# ATmega32.net
KiCad netlist of a schematic drawn in Altium Designer
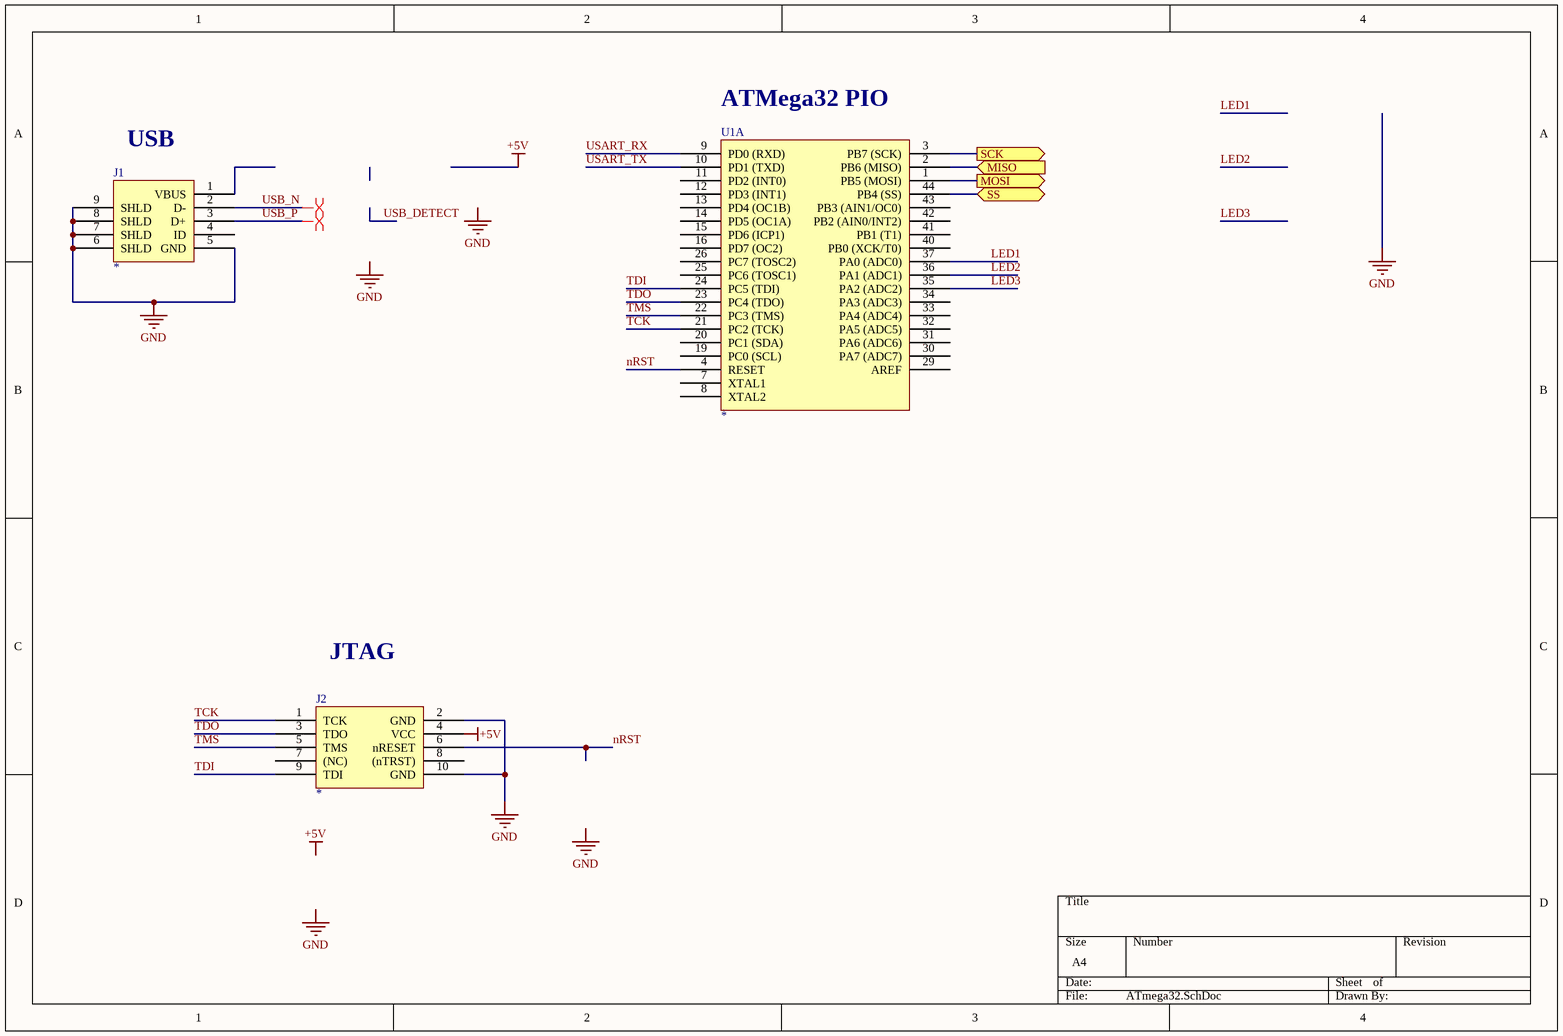
[diagram p0: ATmega32.SchDoc]

(export (version "E")
  (design (tool "Eeschema 10.0.6"))
  (components
    (comp (ref "J1") (value "*") (libsource (lib "Parts") (part "USB MICRO B")))
    (comp (ref "J2") (value "*") (libsource (lib "Parts") (part "JTAG Header")))
    (comp (ref "U1") (value "*") (libsource (lib "Parts") (part "ATmega32")))
  )
  (nets
    (net (code "1") (name "+5V") (class "Default")
      (node (ref "J2") (pin "4") (pinfunction "VCC_4") (pintype "passive"))
    )
    (net (code "2") (name "/LED1") (class "Default")
      (node (ref "U1") (pin "37") (pinfunction "PA0_(ADC0)_37") (pintype "passive"))
    )
    (net (code "3") (name "/LED2") (class "Default")
      (node (ref "U1") (pin "36") (pinfunction "PA1_(ADC1)_36") (pintype "passive"))
    )
    (net (code "4") (name "/LED3") (class "Default")
      (node (ref "U1") (pin "35") (pinfunction "PA2_(ADC2)_35") (pintype "passive"))
    )
    (net (code "5") (name "/MISO") (class "Default")
      (node (ref "U1") (pin "2") (pinfunction "PB6_(MISO)_2") (pintype "passive"))
    )
    (net (code "6") (name "/MOSI") (class "Default")
      (node (ref "U1") (pin "1") (pinfunction "PB5_(MOSI)_1") (pintype "passive"))
    )
    (net (code "7") (name "/SCK") (class "Default")
      (node (ref "U1") (pin "3") (pinfunction "PB7_(SCK)_3") (pintype "passive"))
    )
    (net (code "8") (name "/SS") (class "Default")
      (node (ref "U1") (pin "44") (pinfunction "PB4_(SS)_44") (pintype "passive"))
    )
    (net (code "9") (name "/TCK") (class "Default")
      (node (ref "J2") (pin "1") (pinfunction "TCK_1") (pintype "passive"))
      (node (ref "U1") (pin "21") (pinfunction "PC2_(TCK)_21") (pintype "passive"))
    )
    (net (code "10") (name "/TDI") (class "Default")
      (node (ref "J2") (pin "9") (pinfunction "TDI_9") (pintype "passive"))
      (node (ref "U1") (pin "24") (pinfunction "PC5_(TDI)_24") (pintype "passive"))
    )
    (net (code "11") (name "/TDO") (class "Default")
      (node (ref "J2") (pin "3") (pinfunction "TDO_3") (pintype "passive"))
      (node (ref "U1") (pin "23") (pinfunction "PC4_(TDO)_23") (pintype "passive"))
    )
    (net (code "12") (name "/TMS") (class "Default")
      (node (ref "J2") (pin "5") (pinfunction "TMS_5") (pintype "passive"))
      (node (ref "U1") (pin "22") (pinfunction "PC3_(TMS)_22") (pintype "passive"))
    )
    (net (code "13") (name "/USART_RX") (class "Default")
      (node (ref "U1") (pin "9") (pinfunction "PD0_(RXD)_9") (pintype "passive"))
    )
    (net (code "14") (name "/USART_TX") (class "Default")
      (node (ref "U1") (pin "10") (pinfunction "PD1_(TXD)_10") (pintype "passive"))
    )
    (net (code "16") (name "/USB_N") (class "Default")
      (node (ref "J1") (pin "2") (pinfunction "D-_2") (pintype "passive"))
    )
    (net (code "17") (name "/USB_P") (class "Default")
      (node (ref "J1") (pin "3") (pinfunction "D+_3") (pintype "passive"))
    )
    (net (code "18") (name "/nRST") (class "Default")
      (node (ref "J2") (pin "6") (pinfunction "nRESET_6") (pintype "passive"))
      (node (ref "U1") (pin "4") (pinfunction "RESET_4") (pintype "passive"))
    )
    (net (code "19") (name "GND") (class "Default")
      (node (ref "J1") (pin "5") (pinfunction "GND_5") (pintype "passive"))
      (node (ref "J1") (pin "6") (pinfunction "SHLD_6") (pintype "passive"))
      (node (ref "J1") (pin "7") (pinfunction "SHLD_7") (pintype "passive"))
      (node (ref "J1") (pin "8") (pinfunction "SHLD_8") (pintype "passive"))
      (node (ref "J1") (pin "9") (pinfunction "SHLD_9") (pintype "passive"))
      (node (ref "J2") (pin "10") (pinfunction "GND_10") (pintype "passive"))
      (node (ref "J2") (pin "2") (pinfunction "GND_2") (pintype "passive"))
    )
    (net (code "20") (name "unconnected-(J1-ID-Pad4)") (class "Default")
      (node (ref "J1") (pin "4") (pinfunction "ID_4") (pintype "passive"))
    )
    (net (code "21") (name "unconnected-(J1-VBUS-Pad1)") (class "Default")
      (node (ref "J1") (pin "1") (pinfunction "VBUS_1") (pintype "passive"))
    )
    (net (code "22") (name "unconnected-(J2-(NC)-Pad7)") (class "Default")
      (node (ref "J2") (pin "7") (pinfunction "(NC)_7") (pintype "passive"))
    )
    (net (code "23") (name "unconnected-(J2-(nTRST)-Pad8)") (class "Default")
      (node (ref "J2") (pin "8") (pinfunction "(nTRST)_8") (pintype "passive"))
    )
    (net (code "24") (name "unconnected-(U1A-AREF-Pad29)") (class "Default")
      (node (ref "U1") (pin "29") (pinfunction "AREF_29") (pintype "passive"))
    )
    (net (code "25") (name "unconnected-(U1A-PA3_(ADC3)-Pad34)") (class "Default")
      (node (ref "U1") (pin "34") (pinfunction "PA3_(ADC3)_34") (pintype "passive"))
    )
    (net (code "26") (name "unconnected-(U1A-PA4_(ADC4)-Pad33)") (class "Default")
      (node (ref "U1") (pin "33") (pinfunction "PA4_(ADC4)_33") (pintype "passive"))
    )
    (net (code "27") (name "unconnected-(U1A-PA5_(ADC5)-Pad32)") (class "Default")
      (node (ref "U1") (pin "32") (pinfunction "PA5_(ADC5)_32") (pintype "passive"))
    )
    (net (code "28") (name "unconnected-(U1A-PA6_(ADC6)-Pad31)") (class "Default")
      (node (ref "U1") (pin "31") (pinfunction "PA6_(ADC6)_31") (pintype "passive"))
    )
    (net (code "29") (name "unconnected-(U1A-PA7_(ADC7)-Pad30)") (class "Default")
      (node (ref "U1") (pin "30") (pinfunction "PA7_(ADC7)_30") (pintype "passive"))
    )
    (net (code "30") (name "unconnected-(U1A-PB0_(XCK{slash}T0)-Pad40)") (class "Default")
      (node (ref "U1") (pin "40") (pinfunction "PB0_(XCK/T0)_40") (pintype "passive"))
    )
    (net (code "31") (name "unconnected-(U1A-PB1_(T1)-Pad41)") (class "Default")
      (node (ref "U1") (pin "41") (pinfunction "PB1_(T1)_41") (pintype "passive"))
    )
    (net (code "32") (name "unconnected-(U1A-PB2_(AIN0{slash}INT2)-Pad42)") (class "Default")
      (node (ref "U1") (pin "42") (pinfunction "PB2_(AIN0/INT2)_42") (pintype "passive"))
    )
    (net (code "33") (name "unconnected-(U1A-PB3_(AIN1{slash}OC0)-Pad43)") (class "Default")
      (node (ref "U1") (pin "43") (pinfunction "PB3_(AIN1/OC0)_43") (pintype "passive"))
    )
    (net (code "34") (name "unconnected-(U1A-PC0_(SCL)-Pad19)") (class "Default")
      (node (ref "U1") (pin "19") (pinfunction "PC0_(SCL)_19") (pintype "passive"))
    )
    (net (code "35") (name "unconnected-(U1A-PC1_(SDA)-Pad20)") (class "Default")
      (node (ref "U1") (pin "20") (pinfunction "PC1_(SDA)_20") (pintype "passive"))
    )
    (net (code "36") (name "unconnected-(U1A-PC6_(TOSC1)-Pad25)") (class "Default")
      (node (ref "U1") (pin "25") (pinfunction "PC6_(TOSC1)_25") (pintype "passive"))
    )
    (net (code "37") (name "unconnected-(U1A-PC7_(TOSC2)-Pad26)") (class "Default")
      (node (ref "U1") (pin "26") (pinfunction "PC7_(TOSC2)_26") (pintype "passive"))
    )
    (net (code "38") (name "unconnected-(U1A-PD2_(INT0)-Pad11)") (class "Default")
      (node (ref "U1") (pin "11") (pinfunction "PD2_(INT0)_11") (pintype "passive"))
    )
    (net (code "39") (name "unconnected-(U1A-PD3_(INT1)-Pad12)") (class "Default")
      (node (ref "U1") (pin "12") (pinfunction "PD3_(INT1)_12") (pintype "passive"))
    )
    (net (code "40") (name "unconnected-(U1A-PD4_(OC1B)-Pad13)") (class "Default")
      (node (ref "U1") (pin "13") (pinfunction "PD4_(OC1B)_13") (pintype "passive"))
    )
    (net (code "41") (name "unconnected-(U1A-PD5_(OC1A)-Pad14)") (class "Default")
      (node (ref "U1") (pin "14") (pinfunction "PD5_(OC1A)_14") (pintype "passive"))
    )
    (net (code "42") (name "unconnected-(U1A-PD6_(ICP1)-Pad15)") (class "Default")
      (node (ref "U1") (pin "15") (pinfunction "PD6_(ICP1)_15") (pintype "passive"))
    )
    (net (code "43") (name "unconnected-(U1A-PD7_(OC2)-Pad16)") (class "Default")
      (node (ref "U1") (pin "16") (pinfunction "PD7_(OC2)_16") (pintype "passive"))
    )
    (net (code "44") (name "unconnected-(U1A-XTAL1-Pad7)") (class "Default")
      (node (ref "U1") (pin "7") (pinfunction "XTAL1_7") (pintype "passive"))
    )
    (net (code "45") (name "unconnected-(U1A-XTAL2-Pad8)") (class "Default")
      (node (ref "U1") (pin "8") (pinfunction "XTAL2_8") (pintype "passive"))
    )
  )
)
